# tempsensor.net
KiCad netlist of a schematic drawn in EAGLE
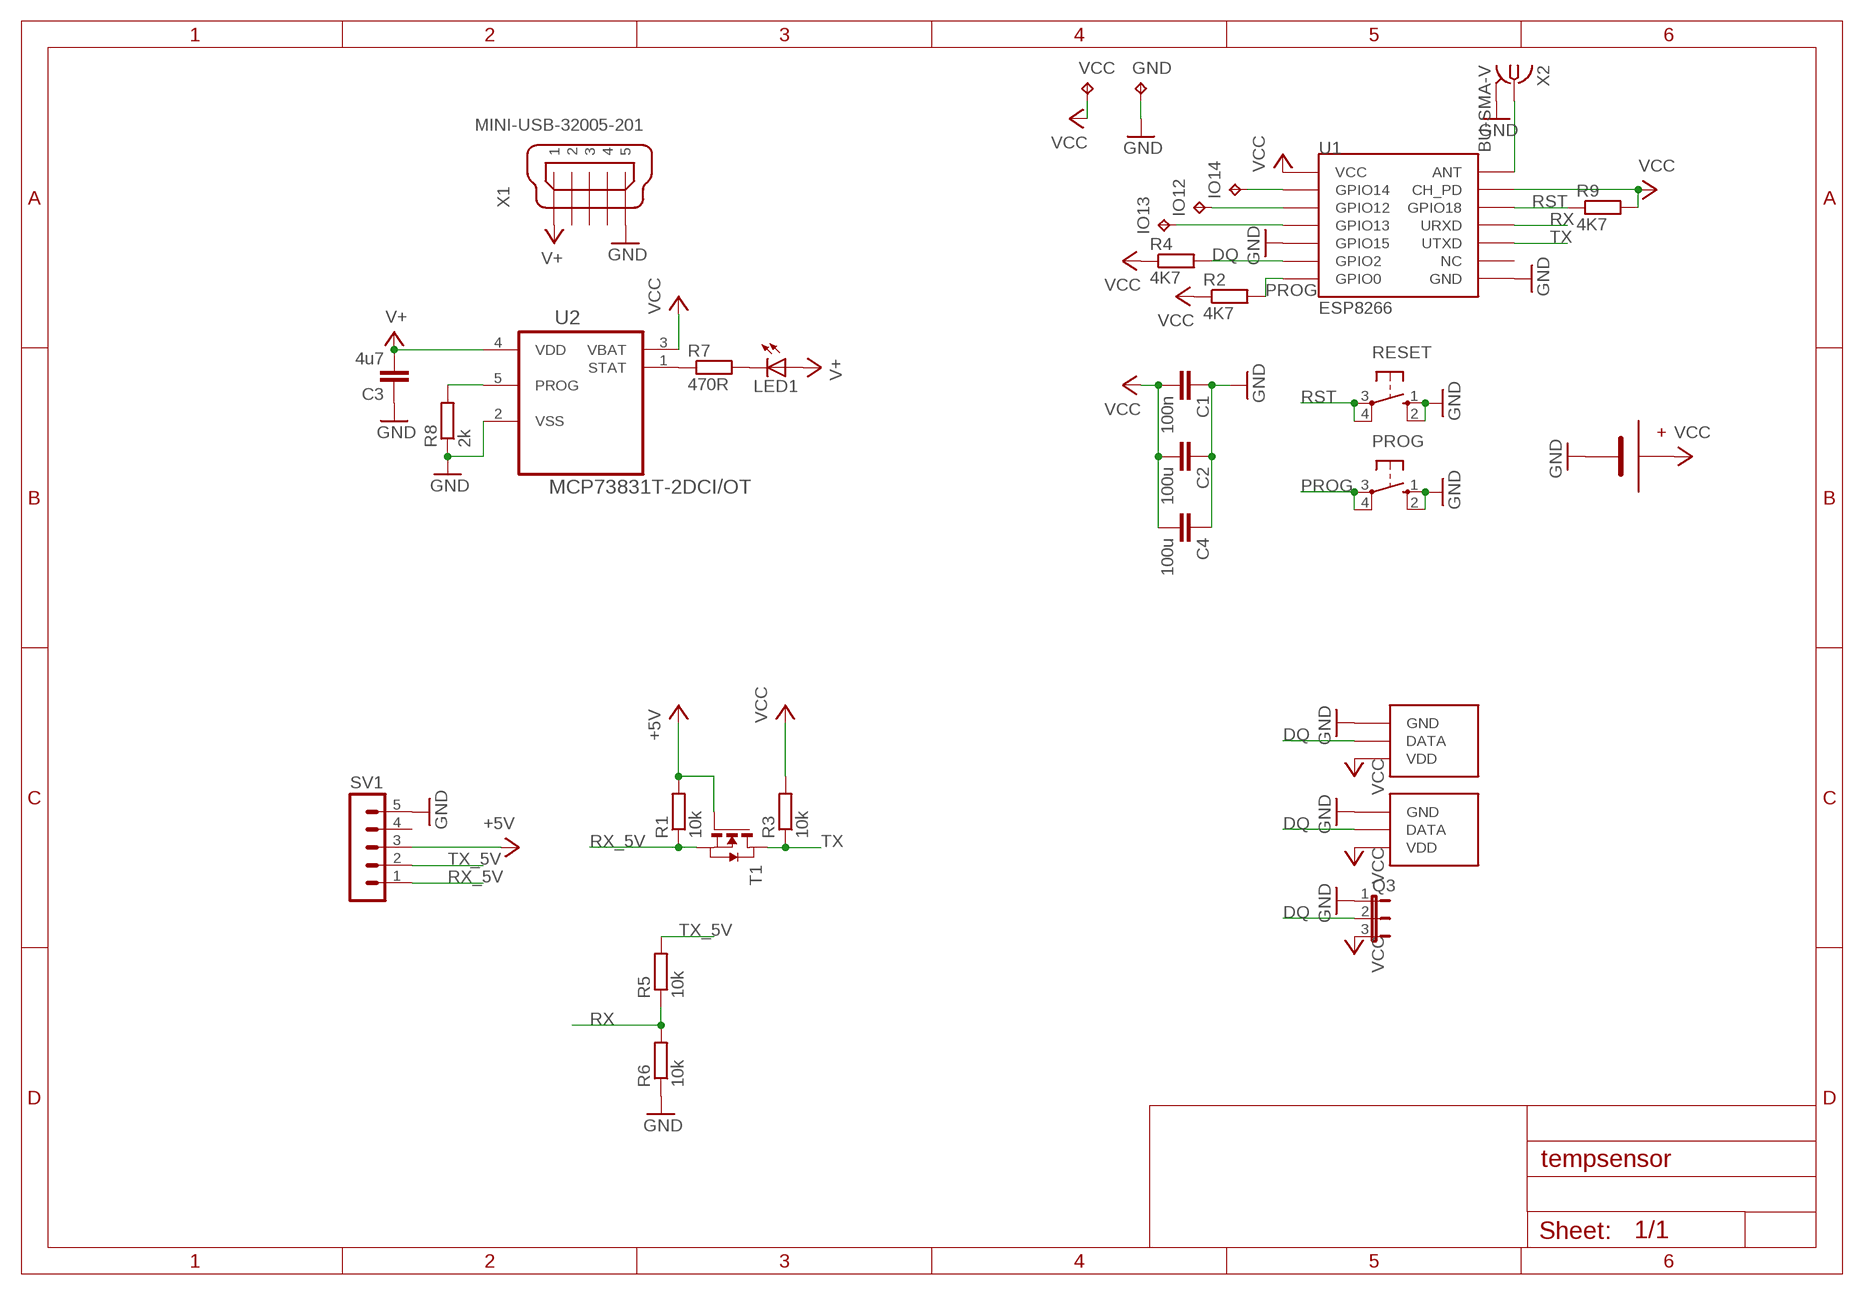
[diagram p0: schematic, sheet 1]

(export (version "E")
  (design (tool "Eeschema 10.0.6"))
  (components
    (comp (ref "C1")
      (value "100n")
      (footprint "eagle-import:C0805")
      (libsource (lib "eagle-import") (part "C-EUC0805"))
    )
    (comp (ref "C2")
      (value "100u")
      (footprint "eagle-import:C1206")
      (libsource (lib "eagle-import") (part "C-EUC1206"))
    )
    (comp (ref "C3")
      (value "4u7")
      (footprint "eagle-import:C0805")
      (libsource (lib "eagle-import") (part "C-EUC0805"))
    )
    (comp (ref "C4")
      (value "100u")
      (footprint "eagle-import:C1206")
      (libsource (lib "eagle-import") (part "C-EUC1206"))
    )
    (comp (ref "GND")
      (value "TPPAD1-13")
      (footprint "eagle-import:P1-13")
      (libsource (lib "eagle-import") (part "TPPAD1-13"))
    )
    (comp (ref "IO12")
      (value "TPPAD1-13")
      (footprint "eagle-import:P1-13")
      (libsource (lib "eagle-import") (part "TPPAD1-13"))
    )
    (comp (ref "IO13")
      (value "TPPAD1-13")
      (footprint "eagle-import:P1-13")
      (libsource (lib "eagle-import") (part "TPPAD1-13"))
    )
    (comp (ref "IO14")
      (value "TPPAD1-13")
      (footprint "eagle-import:P1-13")
      (libsource (lib "eagle-import") (part "TPPAD1-13"))
    )
    (comp (ref "LED1")
      (value "LEDCHIPLED_0805")
      (footprint "eagle-import:CHIPLED_0805")
      (libsource (lib "eagle-import") (part "LEDCHIPLED_0805"))
    )
    (comp (ref "PROG")
      (value "10-XX")
      (footprint "eagle-import:B3F-10XX")
      (fields (field (name "MPN") "B3F-1000"))
      (libsource (lib "eagle-import") (part "10-XX"))
    )
    (comp (ref "Q1")
      (value "DS18X20TO92")
      (footprint "eagle-import:TO92")
      (libsource (lib "eagle-import") (part "DS18X20TO92"))
    )
    (comp (ref "Q2")
      (value "DS18X20SO-8")
      (footprint "eagle-import:SO08WIDE")
      (libsource (lib "eagle-import") (part "DS18X20SO-8"))
    )
    (comp (ref "Q3")
      (value "JP2E")
      (footprint "eagle-import:JP2")
      (libsource (lib "eagle-import") (part "JP2E"))
    )
    (comp (ref "R1")
      (value "10k")
      (footprint "eagle-import:M0805")
      (libsource (lib "eagle-import") (part "R-EU_M0805"))
    )
    (comp (ref "R2")
      (value "4K7")
      (footprint "eagle-import:M0805")
      (libsource (lib "eagle-import") (part "R-EU_M0805"))
    )
    (comp (ref "R3")
      (value "10k")
      (footprint "eagle-import:M0805")
      (libsource (lib "eagle-import") (part "R-EU_M0805"))
    )
    (comp (ref "R4")
      (value "4K7")
      (footprint "eagle-import:M0805")
      (libsource (lib "eagle-import") (part "R-EU_M0805"))
    )
    (comp (ref "R5")
      (value "10k")
      (footprint "eagle-import:M0805")
      (libsource (lib "eagle-import") (part "R-EU_M0805"))
    )
    (comp (ref "R6")
      (value "10k")
      (footprint "eagle-import:M0805")
      (libsource (lib "eagle-import") (part "R-EU_M0805"))
    )
    (comp (ref "R7")
      (value "470R")
      (footprint "eagle-import:M0805")
      (libsource (lib "eagle-import") (part "R-EU_M0805"))
    )
    (comp (ref "R8")
      (value "2k")
      (footprint "eagle-import:M0805")
      (libsource (lib "eagle-import") (part "R-EU_M0805"))
    )
    (comp (ref "R9")
      (value "4K7")
      (footprint "eagle-import:M0805")
      (libsource (lib "eagle-import") (part "R-EU_M0805"))
    )
    (comp (ref "RESET")
      (value "10-XX")
      (footprint "eagle-import:B3F-10XX")
      (fields (field (name "MPN") "B3F-1000"))
      (libsource (lib "eagle-import") (part "10-XX"))
    )
    (comp (ref "SV1")
      (value "MA05-1")
      (footprint "eagle-import:MA05-1")
      (libsource (lib "eagle-import") (part "MA05-1"))
    )
    (comp (ref "T1")
      (value "NMOSSOT23")
      (footprint "eagle-import:SOT-23")
      (libsource (lib "eagle-import") (part "NMOSSOT23"))
    )
    (comp (ref "U$2")
      (value "18650-BATTERHOLDERHA1X18650")
      (footprint "eagle-import:HA1X18650")
      (libsource (lib "eagle-import") (part "18650-BATTERHOLDERHA1X18650"))
    )
    (comp (ref "U1")
      (value "ESP8266")
      (footprint "eagle-import:ESP-03")
      (libsource (lib "eagle-import") (part "ESP8266"))
    )
    (comp (ref "U2")
      (value "MCP73831T-2DCI/OT")
      (footprint "eagle-import:SOT95P270X145-5N")
      (libsource (lib "eagle-import") (part "MCP73831T-2DCI/OT"))
    )
    (comp (ref "VCC")
      (value "TPPAD1-13")
      (footprint "eagle-import:P1-13")
      (libsource (lib "eagle-import") (part "TPPAD1-13"))
    )
    (comp (ref "X1")
      (value "MINI-USB-32005-201")
      (footprint "eagle-import:32005-201")
      (libsource (lib "eagle-import") (part "MINI-USB-32005-201"))
    )
    (comp (ref "X2")
      (value "BU-SMA-V")
      (footprint "eagle-import:BU-SMA-V")
      (libsource (lib "eagle-import") (part "BU-SMA-V"))
    )
  )
  (nets
    (net (code "1") (name "+5V") (class "Default")
      (node (ref "R1") (pin "2") (pinfunction "2_2") (pintype "passive"))
      (node (ref "SV1") (pin "3") (pinfunction "3_3") (pintype "passive"))
      (node (ref "T1") (pin "3") (pinfunction "G_3") (pintype "passive"))
    )
    (net (code "2") (name "/DQ") (class "Default")
      (node (ref "Q1") (pin "2") (pinfunction "DATA_2") (pintype "bidirectional"))
      (node (ref "Q2") (pin "4") (pinfunction "DATA_4") (pintype "bidirectional"))
      (node (ref "Q3") (pin "2") (pinfunction "2_2") (pintype "passive"))
      (node (ref "R4") (pin "2") (pinfunction "2_2") (pintype "passive"))
      (node (ref "U1") (pin "GPIO2") (pinfunction "GPIO2_GPIO2") (pintype "bidirectional"))
    )
    (net (code "3") (name "/PROG") (class "Default")
      (node (ref "PROG") (pin "3") (pinfunction "P_3") (pintype "passive"))
      (node (ref "PROG") (pin "4") (pinfunction "P1_4") (pintype "passive"))
      (node (ref "R2") (pin "2") (pinfunction "2_2") (pintype "passive"))
      (node (ref "U1") (pin "GPIO0") (pinfunction "GPIO0_GPIO0") (pintype "bidirectional"))
    )
    (net (code "4") (name "/RST") (class "Default")
      (node (ref "R9") (pin "1") (pinfunction "1_1") (pintype "passive"))
      (node (ref "RESET") (pin "3") (pinfunction "P_3") (pintype "passive"))
      (node (ref "RESET") (pin "4") (pinfunction "P1_4") (pintype "passive"))
      (node (ref "U1") (pin "GPIO18") (pinfunction "GPIO18_GPIO18") (pintype "bidirectional"))
    )
    (net (code "5") (name "/RX") (class "Default")
      (node (ref "R5") (pin "1") (pinfunction "1_1") (pintype "passive"))
      (node (ref "R6") (pin "2") (pinfunction "2_2") (pintype "passive"))
      (node (ref "U1") (pin "URXD") (pinfunction "URXD_URXD") (pintype "bidirectional"))
    )
    (net (code "6") (name "/RX_5V") (class "Default")
      (node (ref "R1") (pin "1") (pinfunction "1_1") (pintype "passive"))
      (node (ref "SV1") (pin "1") (pinfunction "1_1") (pintype "passive"))
      (node (ref "T1") (pin "2") (pinfunction "S_2") (pintype "passive"))
    )
    (net (code "7") (name "/TX") (class "Default")
      (node (ref "R3") (pin "1") (pinfunction "1_1") (pintype "passive"))
      (node (ref "T1") (pin "1") (pinfunction "D_1") (pintype "passive"))
      (node (ref "U1") (pin "UTXD") (pinfunction "UTXD_UTXD") (pintype "bidirectional"))
    )
    (net (code "8") (name "/TX_5V") (class "Default")
      (node (ref "R5") (pin "2") (pinfunction "2_2") (pintype "passive"))
      (node (ref "SV1") (pin "2") (pinfunction "2_2") (pintype "passive"))
    )
    (net (code "9") (name "GND") (class "Default")
      (node (ref "C1") (pin "1") (pinfunction "1_1") (pintype "passive"))
      (node (ref "C2") (pin "1") (pinfunction "1_1") (pintype "passive"))
      (node (ref "C3") (pin "1") (pinfunction "1_1") (pintype "passive"))
      (node (ref "C4") (pin "1") (pinfunction "1_1") (pintype "passive"))
      (node (ref "GND") (pin "TP") (pinfunction "TP_TP") (pintype "input"))
      (node (ref "PROG") (pin "1") (pinfunction "S_1") (pintype "passive"))
      (node (ref "PROG") (pin "2") (pinfunction "S1_2") (pintype "passive"))
      (node (ref "Q1") (pin "3") (pinfunction "GND_3") (pintype "power_in"))
      (node (ref "Q2") (pin "5") (pinfunction "GND_5") (pintype "power_in"))
      (node (ref "Q3") (pin "1") (pinfunction "1_1") (pintype "passive"))
      (node (ref "R6") (pin "1") (pinfunction "1_1") (pintype "passive"))
      (node (ref "R8") (pin "1") (pinfunction "1_1") (pintype "passive"))
      (node (ref "RESET") (pin "1") (pinfunction "S_1") (pintype "passive"))
      (node (ref "RESET") (pin "2") (pinfunction "S1_2") (pintype "passive"))
      (node (ref "SV1") (pin "5") (pinfunction "5_5") (pintype "passive"))
      (node (ref "U$2") (pin "P$1") (pinfunction "P$1_P$1") (pintype "power_in"))
      (node (ref "U1") (pin "GND") (pinfunction "GND_GND") (pintype "bidirectional"))
      (node (ref "U1") (pin "GPIO15") (pinfunction "GPIO15_GPIO15") (pintype "bidirectional"))
      (node (ref "U2") (pin "2") (pinfunction "VSS_2") (pintype "power_in"))
      (node (ref "X1") (pin "5") (pinfunction "5_5") (pintype "passive"))
      (node (ref "X2") (pin "2") (pinfunction "2_2") (pintype "passive"))
      (node (ref "X2") (pin "3") (pinfunction "2_3") (pintype "passive"))
      (node (ref "X2") (pin "4") (pinfunction "2_4") (pintype "passive"))
      (node (ref "X2") (pin "5") (pinfunction "2_5") (pintype "passive"))
    )
    (net (code "10") (name "Net-(IO12-PadTP)") (class "Default")
      (node (ref "IO12") (pin "TP") (pinfunction "TP_TP") (pintype "input"))
      (node (ref "U1") (pin "GPIO12") (pinfunction "GPIO12_GPIO12") (pintype "bidirectional"))
    )
    (net (code "11") (name "Net-(IO13-PadTP)") (class "Default")
      (node (ref "IO13") (pin "TP") (pinfunction "TP_TP") (pintype "input"))
      (node (ref "U1") (pin "GPIO13") (pinfunction "GPIO13_GPIO13") (pintype "bidirectional"))
    )
    (net (code "12") (name "Net-(IO14-PadTP)") (class "Default")
      (node (ref "IO14") (pin "TP") (pinfunction "TP_TP") (pintype "input"))
      (node (ref "U1") (pin "GPIO14") (pinfunction "GPIO14_GPIO14") (pintype "bidirectional"))
    )
    (net (code "13") (name "Net-(LED1-PadC)") (class "Default")
      (node (ref "LED1") (pin "C") (pinfunction "C_C") (pintype "passive"))
      (node (ref "R7") (pin "2") (pinfunction "2_2") (pintype "passive"))
    )
    (net (code "14") (name "Net-(U1-PadANT)") (class "Default")
      (node (ref "U1") (pin "ANT") (pinfunction "ANT_ANT") (pintype "bidirectional"))
      (node (ref "X2") (pin "1") (pinfunction "1_1") (pintype "passive"))
    )
    (net (code "15") (name "Net-(U2-PROG)") (class "Default")
      (node (ref "R8") (pin "2") (pinfunction "2_2") (pintype "passive"))
      (node (ref "U2") (pin "5") (pinfunction "PROG_5") (pintype "input"))
    )
    (net (code "16") (name "Net-(U2-STAT)") (class "Default")
      (node (ref "R7") (pin "1") (pinfunction "1_1") (pintype "passive"))
      (node (ref "U2") (pin "1") (pinfunction "STAT_1") (pintype "output"))
    )
    (net (code "17") (name "V+") (class "Default")
      (node (ref "C3") (pin "2") (pinfunction "2_2") (pintype "passive"))
      (node (ref "LED1") (pin "A") (pinfunction "A_A") (pintype "passive"))
      (node (ref "U2") (pin "4") (pinfunction "VDD_4") (pintype "power_in"))
      (node (ref "X1") (pin "1") (pinfunction "1_1") (pintype "passive"))
    )
    (net (code "18") (name "VCC") (class "Default")
      (node (ref "C1") (pin "2") (pinfunction "2_2") (pintype "passive"))
      (node (ref "C2") (pin "2") (pinfunction "2_2") (pintype "passive"))
      (node (ref "C4") (pin "2") (pinfunction "2_2") (pintype "passive"))
      (node (ref "Q1") (pin "1") (pinfunction "VDD_1") (pintype "power_in"))
      (node (ref "Q2") (pin "3") (pinfunction "VDD_3") (pintype "power_in"))
      (node (ref "Q3") (pin "3") (pinfunction "3_3") (pintype "passive"))
      (node (ref "R2") (pin "1") (pinfunction "1_1") (pintype "passive"))
      (node (ref "R3") (pin "2") (pinfunction "2_2") (pintype "passive"))
      (node (ref "R4") (pin "1") (pinfunction "1_1") (pintype "passive"))
      (node (ref "R9") (pin "2") (pinfunction "2_2") (pintype "passive"))
      (node (ref "U$2") (pin "P$2") (pinfunction "P$2_P$2") (pintype "power_in"))
      (node (ref "U1") (pin "CH_PD") (pinfunction "CH_PD_CH_PD") (pintype "bidirectional"))
      (node (ref "U1") (pin "VCC") (pinfunction "VCC_VCC") (pintype "bidirectional"))
      (node (ref "U2") (pin "3") (pinfunction "VBAT_3") (pintype "power_in"))
      (node (ref "VCC") (pin "TP") (pinfunction "TP_TP") (pintype "input"))
    )
    (net (code "19") (name "unconnected-(SV1-Pad4)") (class "Default")
      (node (ref "SV1") (pin "4") (pinfunction "4_4") (pintype "passive"))
    )
    (net (code "20") (name "unconnected-(U1-PadNC)") (class "Default")
      (node (ref "U1") (pin "NC") (pinfunction "NC_NC") (pintype "bidirectional"))
    )
    (net (code "21") (name "unconnected-(X1-Pad2)") (class "Default")
      (node (ref "X1") (pin "2") (pinfunction "2_2") (pintype "passive"))
    )
    (net (code "22") (name "unconnected-(X1-Pad3)") (class "Default")
      (node (ref "X1") (pin "3") (pinfunction "3_3") (pintype "passive"))
    )
    (net (code "23") (name "unconnected-(X1-Pad4)") (class "Default")
      (node (ref "X1") (pin "4") (pinfunction "4_4") (pintype "passive"))
    )
  )
)
